# full_charger_v5-3.net
KiCad netlist of a schematic drawn in EAGLE
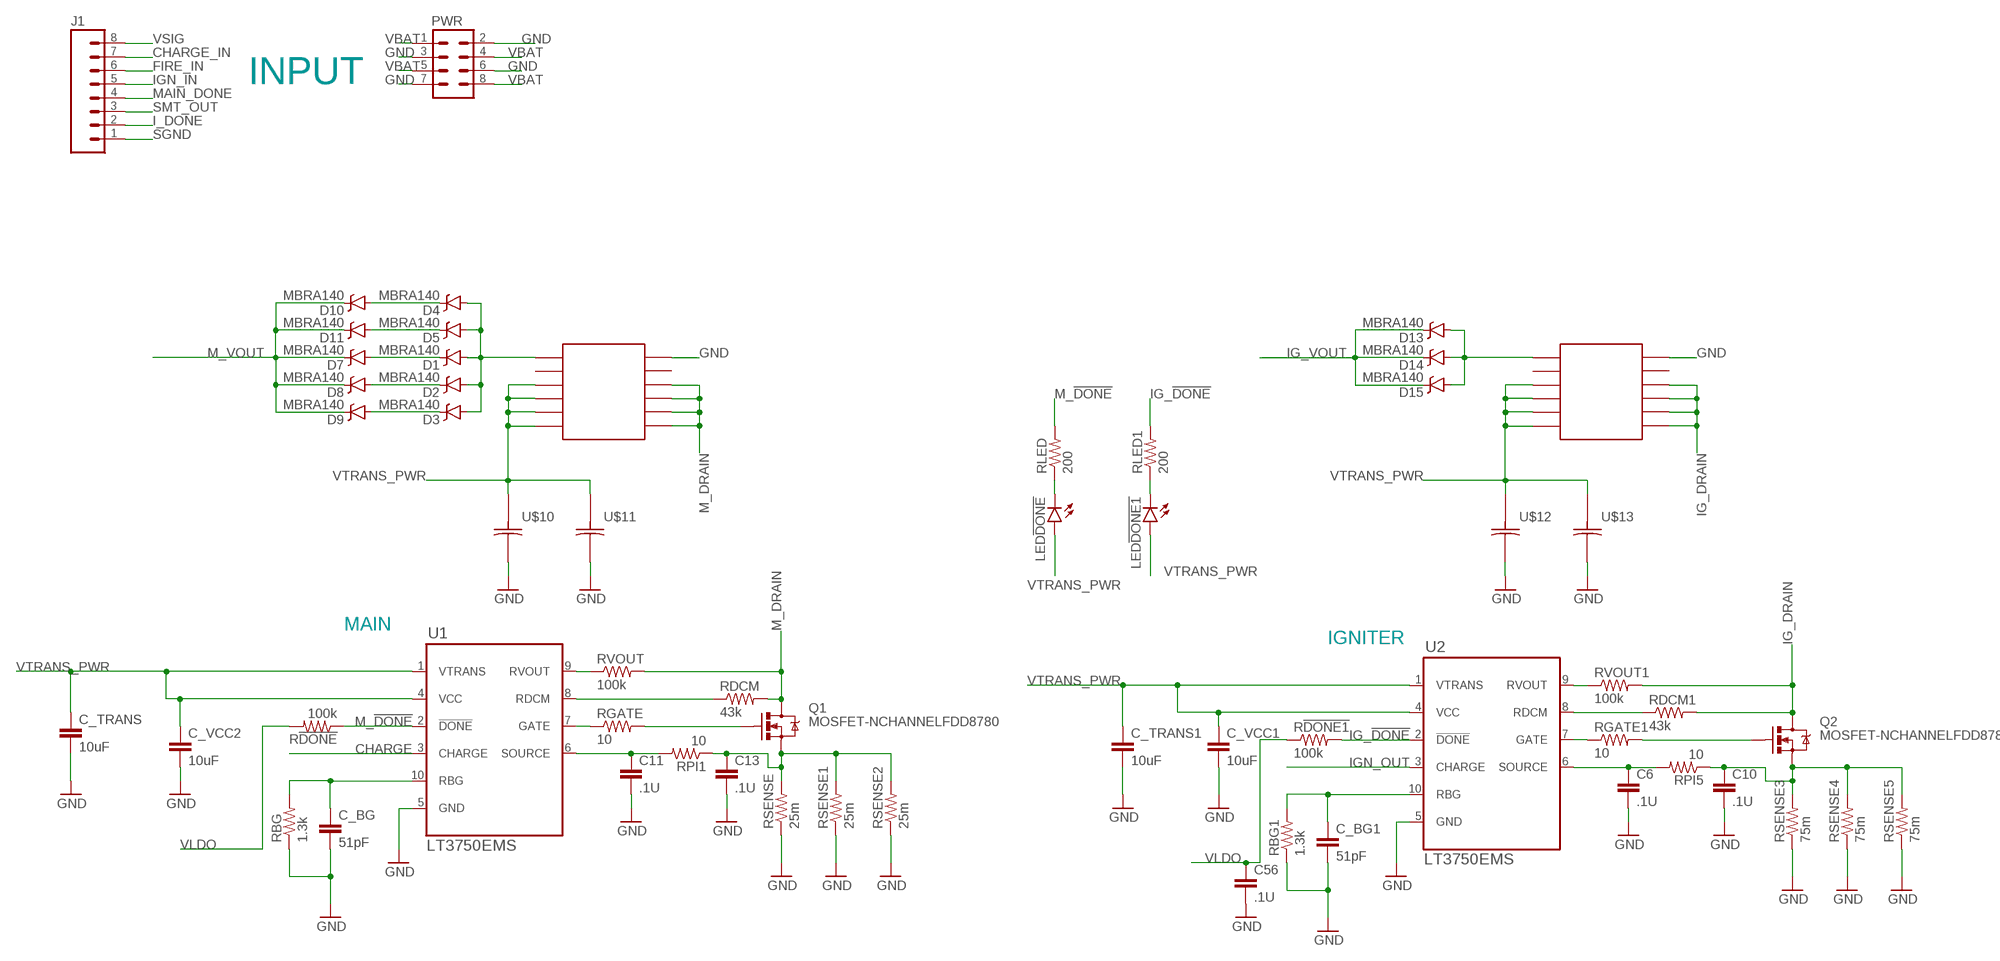
[diagram p0: schematic, sheet 1]
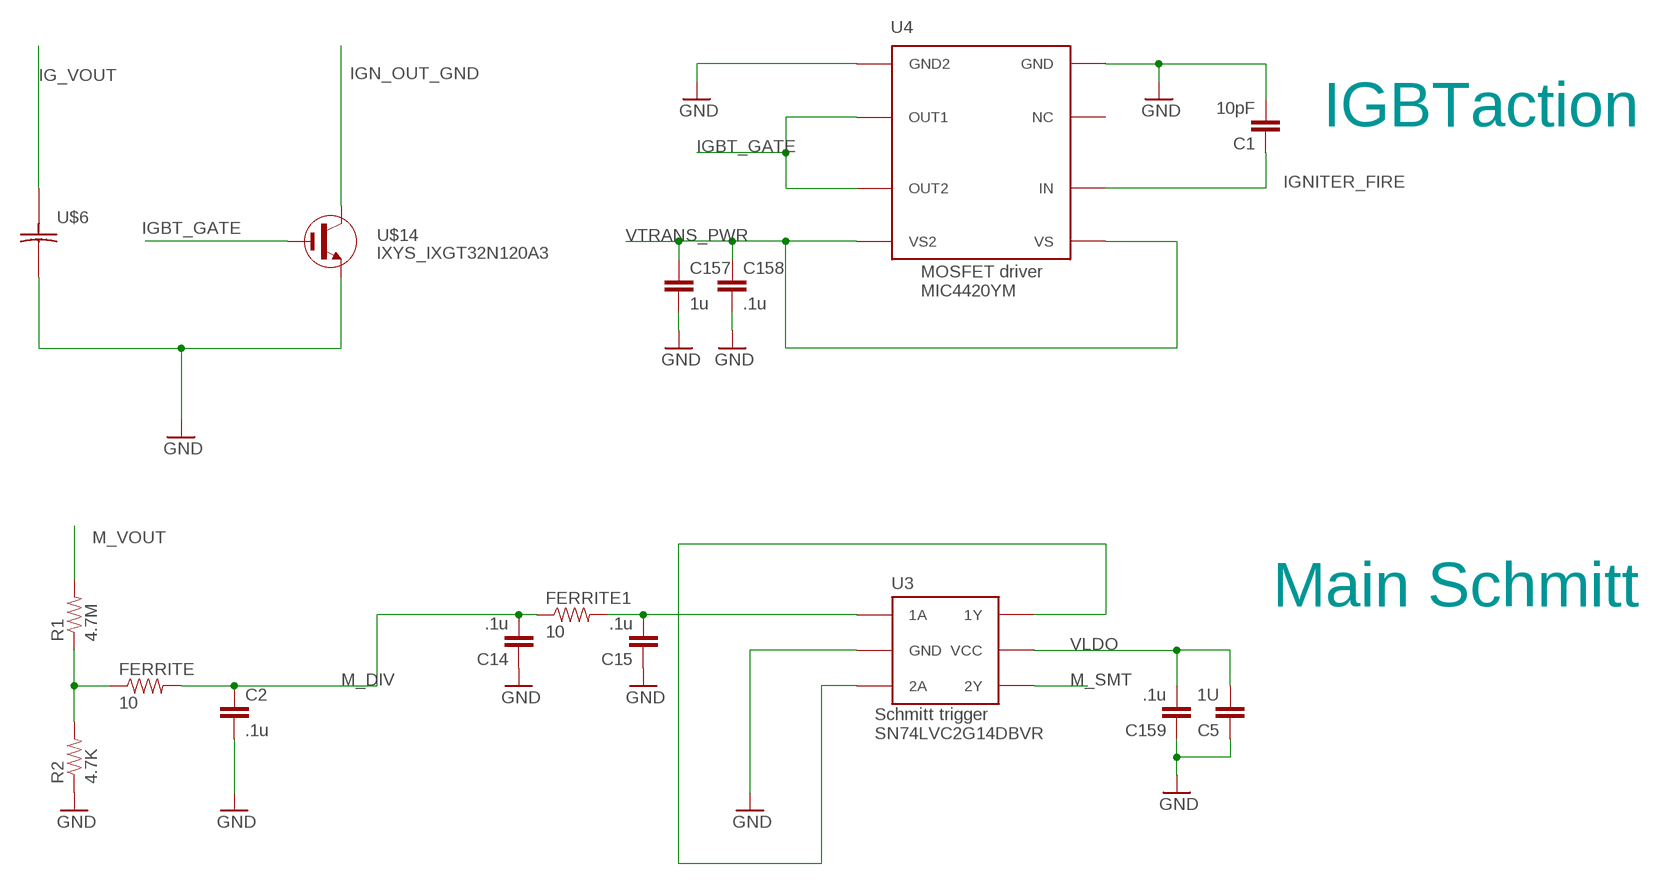
[diagram p1: schematic, sheet 2]
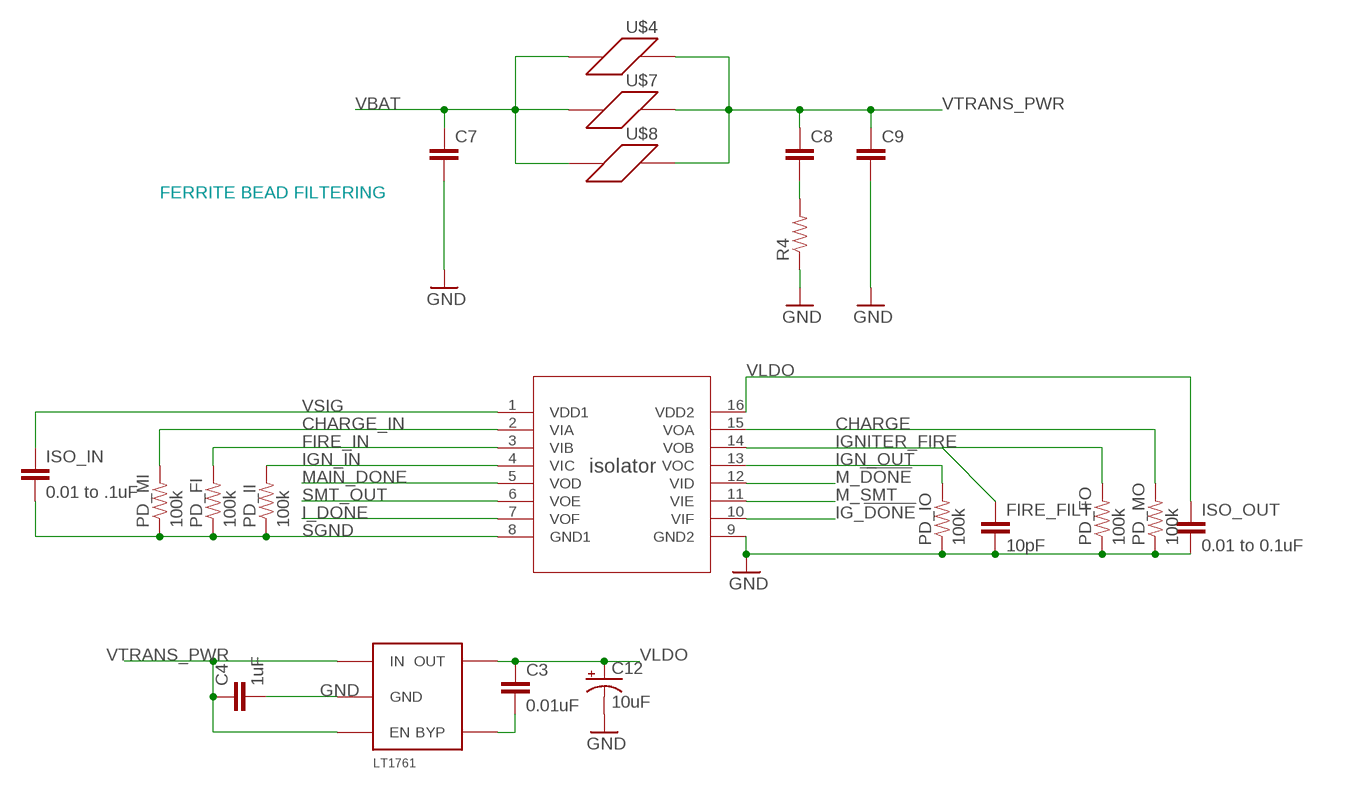
[diagram p2: schematic, sheet 3]

(export (version "E")
  (design (tool "Eeschema 10.0.6"))
  (components
    (comp (ref "ADUM163N")
      (value "ADUM163N1BRZ")
      (footprint "eagle-import:R_16")
      (libsource (lib "eagle-import") (part "ADUM163N1BRZ"))
    )
    (comp (ref "C3")
      (value "0.01uF")
      (footprint "eagle-import:0805")
      (libsource (lib "eagle-import") (part "SparkFun-Passives_CAP0805"))
    )
    (comp (ref "C4")
      (value "1uF")
      (footprint "eagle-import:0805")
      (libsource (lib "eagle-import") (part "SparkFun-Passives_CAP0805"))
    )
    (comp (ref "C7")
      (value "CAP0805")
      (footprint "eagle-import:0805")
      (libsource (lib "eagle-import") (part "CAP0805"))
    )
    (comp (ref "C8")
      (value "CAP0805")
      (footprint "eagle-import:0805")
      (libsource (lib "eagle-import") (part "CAP0805"))
    )
    (comp (ref "C9")
      (value "CAP0805")
      (footprint "eagle-import:0805")
      (libsource (lib "eagle-import") (part "CAP0805"))
    )
    (comp (ref "C12")
      (value "10uF")
      (footprint "eagle-import:EIA3216")
      (libsource (lib "eagle-import") (part "10UF-TANT"))
    )
    (comp (ref "FIRE_FILT")
      (value "10pF")
      (footprint "eagle-import:0805")
      (libsource (lib "eagle-import") (part "SparkFun-Passives_CAP0805"))
    )
    (comp (ref "ISO_IN")
      (value "0.01 to .1uF")
      (footprint "eagle-import:0805")
      (libsource (lib "eagle-import") (part "SparkFun-Passives_CAP0805"))
    )
    (comp (ref "ISO_OUT")
      (value "0.01 to 0.1uF")
      (footprint "eagle-import:0805")
      (libsource (lib "eagle-import") (part "SparkFun-Passives_CAP0805"))
    )
    (comp (ref "LDO")
      (value "LINEAR_LDO_LT1761-X")
      (footprint "eagle-import:SOT-23-5")
      (libsource (lib "eagle-import") (part "LINEAR_LDO_LT1761-X"))
    )
    (comp (ref "PD_FI")
      (value "100k")
      (footprint "eagle-import:0805")
      (libsource (lib "eagle-import") (part "RESISTOR0805-RES"))
    )
    (comp (ref "PD_FO")
      (value "100k")
      (footprint "eagle-import:0805")
      (libsource (lib "eagle-import") (part "RESISTOR0805-RES"))
    )
    (comp (ref "PD_II")
      (value "100k")
      (footprint "eagle-import:0805")
      (libsource (lib "eagle-import") (part "RESISTOR0805-RES"))
    )
    (comp (ref "PD_IO")
      (value "100k")
      (footprint "eagle-import:0805")
      (libsource (lib "eagle-import") (part "RESISTOR0805-RES"))
    )
    (comp (ref "PD_MI")
      (value "100k")
      (footprint "eagle-import:0805")
      (libsource (lib "eagle-import") (part "RESISTOR0805-RES"))
    )
    (comp (ref "PD_MO")
      (value "100k")
      (footprint "eagle-import:0805")
      (libsource (lib "eagle-import") (part "RESISTOR0805-RES"))
    )
    (comp (ref "R4")
      (value "RESISTOR0805-RES")
      (footprint "eagle-import:0805")
      (libsource (lib "eagle-import") (part "RESISTOR0805-RES"))
    )
    (comp (ref "U$4")
      (value "B.L1_FBMJ2125HS420-T")
      (footprint "eagle-import:0805")
      (libsource (lib "eagle-import") (part "B.L1_FBMJ2125HS420-T"))
    )
    (comp (ref "U$7")
      (value "B.L2_FBMH1608HL121-T")
      (footprint "eagle-import:0603")
      (libsource (lib "eagle-import") (part "B.L2_FBMH1608HL121-T"))
    )
    (comp (ref "U$8")
      (value "I.L1_587-3855-1-ND")
      (footprint "eagle-import:1206")
      (libsource (lib "eagle-import") (part "I.L1_587-3855-1-ND"))
    )
    (comp (ref "C1")
      (value "10pF")
      (footprint "eagle-import:0805")
      (libsource (lib "eagle-import") (part "CAP0805"))
    )
    (comp (ref "C2")
      (value ".1u")
      (footprint "eagle-import:0805")
      (libsource (lib "eagle-import") (part "CAP0805"))
    )
    (comp (ref "C5")
      (value "1U")
      (footprint "eagle-import:0805")
      (libsource (lib "eagle-import") (part "CAP0805"))
    )
    (comp (ref "C14")
      (value ".1u")
      (footprint "eagle-import:0805")
      (libsource (lib "eagle-import") (part "CAP0805"))
    )
    (comp (ref "C15")
      (value ".1u")
      (footprint "eagle-import:0805")
      (libsource (lib "eagle-import") (part "CAP0805"))
    )
    (comp (ref "C157")
      (value "1u")
      (footprint "eagle-import:0805")
      (libsource (lib "eagle-import") (part "CAP0805"))
    )
    (comp (ref "C158")
      (value ".1u")
      (footprint "eagle-import:0805")
      (libsource (lib "eagle-import") (part "CAP0805"))
    )
    (comp (ref "C159")
      (value ".1u")
      (footprint "eagle-import:0805")
      (libsource (lib "eagle-import") (part "CAP0805"))
    )
    (comp (ref "FERRITE")
      (value "10")
      (footprint "eagle-import:0805")
      (libsource (lib "eagle-import") (part "RESISTOR0805-RES"))
    )
    (comp (ref "FERRITE1")
      (value "10")
      (footprint "eagle-import:0805")
      (libsource (lib "eagle-import") (part "RESISTOR0805-RES"))
    )
    (comp (ref "R1")
      (value "4.7M")
      (footprint "eagle-import:R2010")
      (libsource (lib "eagle-import") (part "SparkFun-Passives_RESISTOR2010"))
    )
    (comp (ref "R2")
      (value "4.7K")
      (footprint "eagle-import:R2010")
      (libsource (lib "eagle-import") (part "SparkFun-Passives_RESISTOR2010"))
    )
    (comp (ref "U$6")
      (value "KEMET_LDEQH3100KA5N00")
      (footprint "eagle-import:KEMET_F3078")
      (libsource (lib "eagle-import") (part "KEMET_LDEQH3100KA5N00"))
    )
    (comp (ref "U$14")
      (value "IXYS_IXGT32N120A3")
      (footprint "eagle-import:TO-268")
      (libsource (lib "eagle-import") (part "IXYS_IXGT32N120A3"))
    )
    (comp (ref "U3")
      (value "TI_SCHMITTRIGGER_SN74")
      (footprint "eagle-import:SOT-23-6")
      (libsource (lib "eagle-import") (part "TI_SCHMITTRIGGER_SN74"))
    )
    (comp (ref "U4")
      (value "MICREL_MOSFETDRIVER_MIC4420")
      (footprint "eagle-import:8-SOIC")
      (libsource (lib "eagle-import") (part "MICREL_MOSFETDRIVER_MIC4420"))
    )
    (comp (ref "C6")
      (value ".1U")
      (footprint "eagle-import:0805")
      (libsource (lib "eagle-import") (part "CAP0805"))
    )
    (comp (ref "C10")
      (value ".1U")
      (footprint "eagle-import:0805")
      (libsource (lib "eagle-import") (part "CAP0805"))
    )
    (comp (ref "C11")
      (value ".1U")
      (footprint "eagle-import:0805")
      (libsource (lib "eagle-import") (part "CAP0805"))
    )
    (comp (ref "C13")
      (value ".1U")
      (footprint "eagle-import:0805")
      (libsource (lib "eagle-import") (part "CAP0805"))
    )
    (comp (ref "C56")
      (value ".1U")
      (footprint "eagle-import:0805")
      (libsource (lib "eagle-import") (part "CAP0805"))
    )
    (comp (ref "C_BG")
      (value "51pF")
      (footprint "eagle-import:0805")
      (libsource (lib "eagle-import") (part "CAP0805"))
    )
    (comp (ref "C_BG1")
      (value "51pF")
      (footprint "eagle-import:0805")
      (libsource (lib "eagle-import") (part "CAP0805"))
    )
    (comp (ref "C_TRANS")
      (value "10uF")
      (footprint "eagle-import:0805")
      (libsource (lib "eagle-import") (part "CAP0805"))
    )
    (comp (ref "C_TRANS1")
      (value "10uF")
      (footprint "eagle-import:0805")
      (libsource (lib "eagle-import") (part "CAP0805"))
    )
    (comp (ref "C_VCC1")
      (value "10uF")
      (footprint "eagle-import:0805")
      (libsource (lib "eagle-import") (part "CAP0805"))
    )
    (comp (ref "C_VCC2")
      (value "10uF")
      (footprint "eagle-import:0805")
      (libsource (lib "eagle-import") (part "CAP0805"))
    )
    (comp (ref "D1")
      (value "MBRA140")
      (footprint "eagle-import:SMA-DIODE")
      (libsource (lib "eagle-import") (part "MBRA140"))
    )
    (comp (ref "D2")
      (value "MBRA140")
      (footprint "eagle-import:SMA-DIODE")
      (libsource (lib "eagle-import") (part "MBRA140"))
    )
    (comp (ref "D3")
      (value "MBRA140")
      (footprint "eagle-import:SMA-DIODE")
      (libsource (lib "eagle-import") (part "MBRA140"))
    )
    (comp (ref "D4")
      (value "MBRA140")
      (footprint "eagle-import:SMA-DIODE")
      (libsource (lib "eagle-import") (part "MBRA140"))
    )
    (comp (ref "D5")
      (value "MBRA140")
      (footprint "eagle-import:SMA-DIODE")
      (libsource (lib "eagle-import") (part "MBRA140"))
    )
    (comp (ref "D7")
      (value "MBRA140")
      (footprint "eagle-import:SMA-DIODE")
      (libsource (lib "eagle-import") (part "MBRA140"))
    )
    (comp (ref "D8")
      (value "MBRA140")
      (footprint "eagle-import:SMA-DIODE")
      (libsource (lib "eagle-import") (part "MBRA140"))
    )
    (comp (ref "D9")
      (value "MBRA140")
      (footprint "eagle-import:SMA-DIODE")
      (libsource (lib "eagle-import") (part "MBRA140"))
    )
    (comp (ref "D10")
      (value "MBRA140")
      (footprint "eagle-import:SMA-DIODE")
      (libsource (lib "eagle-import") (part "MBRA140"))
    )
    (comp (ref "D11")
      (value "MBRA140")
      (footprint "eagle-import:SMA-DIODE")
      (libsource (lib "eagle-import") (part "MBRA140"))
    )
    (comp (ref "D13")
      (value "MBRA140")
      (footprint "eagle-import:SMA-DIODE")
      (libsource (lib "eagle-import") (part "MBRA140"))
    )
    (comp (ref "D14")
      (value "MBRA140")
      (footprint "eagle-import:SMA-DIODE")
      (libsource (lib "eagle-import") (part "MBRA140"))
    )
    (comp (ref "D15")
      (value "MBRA140")
      (footprint "eagle-import:SMA-DIODE")
      (libsource (lib "eagle-import") (part "MBRA140"))
    )
    (comp (ref "J1")
      (value "M08")
      (footprint "eagle-import:1X08_ROUND")
      (libsource (lib "eagle-import") (part "M08"))
    )
    (comp (ref "LED!DONE")
      (value "LED1206")
      (footprint "eagle-import:LED-1206")
      (libsource (lib "eagle-import") (part "LED1206"))
    )
    (comp (ref "LED!DONE1")
      (value "LED1206")
      (footprint "eagle-import:LED-1206")
      (libsource (lib "eagle-import") (part "LED1206"))
    )
    (comp (ref "PWR")
      (value "M04X2")
      (footprint "eagle-import:2X4")
      (libsource (lib "eagle-import") (part "M04X2"))
    )
    (comp (ref "Q1")
      (value "MOSFET-NCHANNELFDD8780")
      (footprint "eagle-import:DPAK")
      (libsource (lib "eagle-import") (part "MOSFET-NCHANNELFDD8780"))
    )
    (comp (ref "Q2")
      (value "MOSFET-NCHANNELFDD8780")
      (footprint "eagle-import:DPAK")
      (libsource (lib "eagle-import") (part "MOSFET-NCHANNELFDD8780"))
    )
    (comp (ref "R!DONE")
      (value "100k")
      (footprint "eagle-import:0805")
      (libsource (lib "eagle-import") (part "SparkFun-Resistors_RESISTOR0805-RES"))
    )
    (comp (ref "R!DONE1")
      (value "100k")
      (footprint "eagle-import:0805")
      (libsource (lib "eagle-import") (part "SparkFun-Resistors_RESISTOR0805-RES"))
    )
    (comp (ref "RBG")
      (value "1.3k")
      (footprint "eagle-import:0805")
      (libsource (lib "eagle-import") (part "SparkFun-Resistors_RESISTOR0805-RES"))
    )
    (comp (ref "RBG1")
      (value "1.3k")
      (footprint "eagle-import:0805")
      (libsource (lib "eagle-import") (part "SparkFun-Resistors_RESISTOR0805-RES"))
    )
    (comp (ref "RDCM")
      (value "43k")
      (footprint "eagle-import:0805")
      (libsource (lib "eagle-import") (part "SparkFun-Resistors_RESISTOR0805-RES"))
    )
    (comp (ref "RDCM1")
      (value "43k")
      (footprint "eagle-import:0805")
      (libsource (lib "eagle-import") (part "SparkFun-Resistors_RESISTOR0805-RES"))
    )
    (comp (ref "RGATE")
      (value "10")
      (footprint "eagle-import:0805")
      (libsource (lib "eagle-import") (part "SparkFun-Resistors_RESISTOR0805-RES"))
    )
    (comp (ref "RGATE1")
      (value "10")
      (footprint "eagle-import:0805")
      (libsource (lib "eagle-import") (part "SparkFun-Resistors_RESISTOR0805-RES"))
    )
    (comp (ref "RLED")
      (value "200")
      (footprint "eagle-import:0805")
      (libsource (lib "eagle-import") (part "RESISTOR0805-RES"))
    )
    (comp (ref "RLED1")
      (value "200")
      (footprint "eagle-import:0805")
      (libsource (lib "eagle-import") (part "RESISTOR0805-RES"))
    )
    (comp (ref "RPI1")
      (value "10")
      (footprint "eagle-import:0805")
      (libsource (lib "eagle-import") (part "SparkFun-Resistors_RESISTOR0805-RES"))
    )
    (comp (ref "RPI5")
      (value "10")
      (footprint "eagle-import:0805")
      (libsource (lib "eagle-import") (part "SparkFun-Resistors_RESISTOR0805-RES"))
    )
    (comp (ref "RSENSE")
      (value "25m")
      (footprint "eagle-import:1206")
      (libsource (lib "eagle-import") (part "RESISTOR1206"))
    )
    (comp (ref "RSENSE1")
      (value "25m")
      (footprint "eagle-import:1206")
      (libsource (lib "eagle-import") (part "RESISTOR1206"))
    )
    (comp (ref "RSENSE2")
      (value "25m")
      (footprint "eagle-import:1206")
      (libsource (lib "eagle-import") (part "RESISTOR1206"))
    )
    (comp (ref "RSENSE3")
      (value "75m")
      (footprint "eagle-import:1206")
      (libsource (lib "eagle-import") (part "RESISTOR1206"))
    )
    (comp (ref "RSENSE4")
      (value "75m")
      (footprint "eagle-import:1206")
      (libsource (lib "eagle-import") (part "RESISTOR1206"))
    )
    (comp (ref "RSENSE5")
      (value "75m")
      (footprint "eagle-import:1206")
      (libsource (lib "eagle-import") (part "RESISTOR1206"))
    )
    (comp (ref "RVOUT")
      (value "100k")
      (footprint "eagle-import:0805")
      (libsource (lib "eagle-import") (part "SparkFun-Resistors_RESISTOR0805-RES"))
    )
    (comp (ref "RVOUT1")
      (value "100k")
      (footprint "eagle-import:0805")
      (libsource (lib "eagle-import") (part "SparkFun-Resistors_RESISTOR0805-RES"))
    )
    (comp (ref "U$1")
      (value "COILCRAFT_DA2034")
      (footprint "eagle-import:DA2034")
      (libsource (lib "eagle-import") (part "COILCRAFT_DA2034"))
    )
    (comp (ref "U$2")
      (value "COILCRAFT_DA2033")
      (footprint "eagle-import:DA2033")
      (libsource (lib "eagle-import") (part "COILCRAFT_DA2033"))
    )
    (comp (ref "U$10")
      (value "PANASONIC_16SVPG270M")
      (footprint "eagle-import:PANASONIC_SVPG")
      (libsource (lib "eagle-import") (part "PANASONIC_16SVPG270M"))
    )
    (comp (ref "U$11")
      (value "PANASONIC_16SVPG270M")
      (footprint "eagle-import:PANASONIC_SVPG")
      (libsource (lib "eagle-import") (part "PANASONIC_16SVPG270M"))
    )
    (comp (ref "U$12")
      (value "PANASONIC_16SVPG270M")
      (footprint "eagle-import:PANASONIC_SVPG")
      (libsource (lib "eagle-import") (part "PANASONIC_16SVPG270M"))
    )
    (comp (ref "U$13")
      (value "PANASONIC_16SVPG270M")
      (footprint "eagle-import:PANASONIC_SVPG")
      (libsource (lib "eagle-import") (part "PANASONIC_16SVPG270M"))
    )
    (comp (ref "U1")
      (value "LT3750EMS")
      (footprint "eagle-import:MSOP10")
      (libsource (lib "eagle-import") (part "LT3750EMS"))
    )
    (comp (ref "U2")
      (value "LT3750EMS")
      (footprint "eagle-import:MSOP10")
      (libsource (lib "eagle-import") (part "LT3750EMS"))
    )
  )
  (nets
    (net (code "1") (name "CHARGE") (class "Default")
      (node (ref "ADUM163N") (pin "15") (pinfunction "VOA_15") (pintype "passive"))
      (node (ref "PD_MO") (pin "2") (pinfunction "2_2") (pintype "passive"))
      (node (ref "U1") (pin "3") (pinfunction "CHARGE_3") (pintype "bidirectional"))
    )
    (net (code "2") (name "CHARGE_IN") (class "Default")
      (node (ref "ADUM163N") (pin "2") (pinfunction "VIA_2") (pintype "passive"))
      (node (ref "J1") (pin "7") (pinfunction "7_7") (pintype "passive"))
      (node (ref "PD_MI") (pin "2") (pinfunction "2_2") (pintype "passive"))
    )
    (net (code "3") (name "FIRE_IN") (class "Default")
      (node (ref "ADUM163N") (pin "3") (pinfunction "VIB_3") (pintype "passive"))
      (node (ref "J1") (pin "6") (pinfunction "6_6") (pintype "passive"))
      (node (ref "PD_FI") (pin "2") (pinfunction "2_2") (pintype "passive"))
    )
    (net (code "4") (name "GND") (class "Default")
      (node (ref "ADUM163N") (pin "9") (pinfunction "GND2_9") (pintype "passive"))
      (node (ref "C1") (pin "2") (pinfunction "2_2") (pintype "passive"))
      (node (ref "C10") (pin "2") (pinfunction "2_2") (pintype "passive"))
      (node (ref "C11") (pin "2") (pinfunction "2_2") (pintype "passive"))
      (node (ref "C12") (pin "C") (pinfunction "-_C") (pintype "passive"))
      (node (ref "C13") (pin "2") (pinfunction "2_2") (pintype "passive"))
      (node (ref "C14") (pin "1") (pinfunction "1_1") (pintype "passive"))
      (node (ref "C15") (pin "1") (pinfunction "1_1") (pintype "passive"))
      (node (ref "C157") (pin "2") (pinfunction "2_2") (pintype "passive"))
      (node (ref "C158") (pin "2") (pinfunction "2_2") (pintype "passive"))
      (node (ref "C159") (pin "1") (pinfunction "1_1") (pintype "passive"))
      (node (ref "C2") (pin "2") (pinfunction "2_2") (pintype "passive"))
      (node (ref "C4") (pin "2") (pinfunction "2_2") (pintype "passive"))
      (node (ref "C5") (pin "1") (pinfunction "1_1") (pintype "passive"))
      (node (ref "C56") (pin "2") (pinfunction "2_2") (pintype "passive"))
      (node (ref "C6") (pin "2") (pinfunction "2_2") (pintype "passive"))
      (node (ref "C7") (pin "2") (pinfunction "2_2") (pintype "passive"))
      (node (ref "C9") (pin "2") (pinfunction "2_2") (pintype "passive"))
      (node (ref "C_BG") (pin "2") (pinfunction "2_2") (pintype "passive"))
      (node (ref "C_BG1") (pin "2") (pinfunction "2_2") (pintype "passive"))
      (node (ref "C_TRANS") (pin "2") (pinfunction "2_2") (pintype "passive"))
      (node (ref "C_TRANS1") (pin "2") (pinfunction "2_2") (pintype "passive"))
      (node (ref "C_VCC1") (pin "2") (pinfunction "2_2") (pintype "passive"))
      (node (ref "C_VCC2") (pin "2") (pinfunction "2_2") (pintype "passive"))
      (node (ref "FIRE_FILT") (pin "2") (pinfunction "2_2") (pintype "passive"))
      (node (ref "ISO_OUT") (pin "2") (pinfunction "2_2") (pintype "passive"))
      (node (ref "LDO") (pin "P$2") (pinfunction "GND_P$2") (pintype "bidirectional"))
      (node (ref "PD_FO") (pin "1") (pinfunction "1_1") (pintype "passive"))
      (node (ref "PD_IO") (pin "1") (pinfunction "1_1") (pintype "passive"))
      (node (ref "PD_MO") (pin "1") (pinfunction "1_1") (pintype "passive"))
      (node (ref "PWR") (pin "2") (pinfunction "2_2") (pintype "passive"))
      (node (ref "PWR") (pin "3") (pinfunction "3_3") (pintype "passive"))
      (node (ref "PWR") (pin "6") (pinfunction "6_6") (pintype "passive"))
      (node (ref "PWR") (pin "7") (pinfunction "7_7") (pintype "passive"))
      (node (ref "R2") (pin "1") (pinfunction "1_1") (pintype "passive"))
      (node (ref "R4") (pin "1") (pinfunction "1_1") (pintype "passive"))
      (node (ref "RBG") (pin "1") (pinfunction "1_1") (pintype "passive"))
      (node (ref "RBG1") (pin "1") (pinfunction "1_1") (pintype "passive"))
      (node (ref "RSENSE") (pin "1") (pinfunction "1_1") (pintype "passive"))
      (node (ref "RSENSE1") (pin "1") (pinfunction "1_1") (pintype "passive"))
      (node (ref "RSENSE2") (pin "1") (pinfunction "1_1") (pintype "passive"))
      (node (ref "RSENSE3") (pin "1") (pinfunction "1_1") (pintype "passive"))
      (node (ref "RSENSE4") (pin "1") (pinfunction "1_1") (pintype "passive"))
      (node (ref "RSENSE5") (pin "1") (pinfunction "1_1") (pintype "passive"))
      (node (ref "U$1") (pin "P$12") (pinfunction "P$12_P$12") (pintype "bidirectional"))
      (node (ref "U$10") (pin "NEG") (pinfunction "NEG_NEG") (pintype "bidirectional"))
      (node (ref "U$11") (pin "NEG") (pinfunction "NEG_NEG") (pintype "bidirectional"))
      (node (ref "U$12") (pin "NEG") (pinfunction "NEG_NEG") (pintype "bidirectional"))
      (node (ref "U$13") (pin "NEG") (pinfunction "NEG_NEG") (pintype "bidirectional"))
      (node (ref "U$14") (pin "3") (pinfunction "E_3") (pintype "passive"))
      (node (ref "U$2") (pin "P$12") (pinfunction "P$12_P$12") (pintype "bidirectional"))
      (node (ref "U$6") (pin "NEG") (pinfunction "NEG_NEG") (pintype "bidirectional"))
      (node (ref "U1") (pin "5") (pinfunction "GND_5") (pintype "passive"))
      (node (ref "U2") (pin "5") (pinfunction "GND_5") (pintype "passive"))
      (node (ref "U3") (pin "P$2") (pinfunction "GND_P$2") (pintype "bidirectional"))
      (node (ref "U4") (pin "P$4") (pinfunction "GND_P$4") (pintype "bidirectional"))
      (node (ref "U4") (pin "P$5") (pinfunction "GND2_P$5") (pintype "bidirectional"))
    )
    (net (code "5") (name "IGBT_GATE") (class "Default")
      (node (ref "U$14") (pin "1") (pinfunction "G_1") (pintype "passive"))
      (node (ref "U4") (pin "P$6") (pinfunction "OUT1_P$6") (pintype "bidirectional"))
      (node (ref "U4") (pin "P$7") (pinfunction "OUT2_P$7") (pintype "bidirectional"))
    )
    (net (code "6") (name "IGNITER_FIRE") (class "Default")
      (node (ref "ADUM163N") (pin "14") (pinfunction "VOB_14") (pintype "passive"))
      (node (ref "C1") (pin "1") (pinfunction "1_1") (pintype "passive"))
      (node (ref "FIRE_FILT") (pin "1") (pinfunction "1_1") (pintype "passive"))
      (node (ref "PD_FO") (pin "2") (pinfunction "2_2") (pintype "passive"))
      (node (ref "U4") (pin "P$2") (pinfunction "IN_P$2") (pintype "bidirectional"))
    )
    (net (code "7") (name "IGN_IN") (class "Default")
      (node (ref "ADUM163N") (pin "4") (pinfunction "VIC_4") (pintype "passive"))
      (node (ref "J1") (pin "5") (pinfunction "5_5") (pintype "passive"))
      (node (ref "PD_II") (pin "2") (pinfunction "2_2") (pintype "passive"))
    )
    (net (code "8") (name "IGN_OUT") (class "Default")
      (node (ref "ADUM163N") (pin "13") (pinfunction "VOC_13") (pintype "passive"))
      (node (ref "PD_IO") (pin "2") (pinfunction "2_2") (pintype "passive"))
      (node (ref "U2") (pin "3") (pinfunction "CHARGE_3") (pintype "bidirectional"))
    )
    (net (code "9") (name "IGN_OUT_GND") (class "Default")
      (node (ref "U$14") (pin "2") (pinfunction "C_2") (pintype "passive"))
    )
    (net (code "10") (name "IG_DRAIN") (class "Default")
      (node (ref "Q2") (pin "4") (pinfunction "D_4") (pintype "passive"))
      (node (ref "RDCM1") (pin "2") (pinfunction "2_2") (pintype "passive"))
      (node (ref "RVOUT1") (pin "2") (pinfunction "2_2") (pintype "passive"))
      (node (ref "U$2") (pin "P$10") (pinfunction "P$10_P$10") (pintype "bidirectional"))
      (node (ref "U$2") (pin "P$7") (pinfunction "P$7_P$7") (pintype "bidirectional"))
      (node (ref "U$2") (pin "P$8") (pinfunction "P$8_P$8") (pintype "bidirectional"))
      (node (ref "U$2") (pin "P$9") (pinfunction "P$9_P$9") (pintype "bidirectional"))
    )
    (net (code "11") (name "IG_VOUT") (class "Default")
      (node (ref "D13") (pin "C") (pinfunction "C_C") (pintype "passive"))
      (node (ref "D14") (pin "C") (pinfunction "C_C") (pintype "passive"))
      (node (ref "D15") (pin "C") (pinfunction "C_C") (pintype "passive"))
      (node (ref "U$6") (pin "POS") (pinfunction "POS_POS") (pintype "bidirectional"))
    )
    (net (code "12") (name "IG_~{DONE}") (class "Default")
      (node (ref "ADUM163N") (pin "10") (pinfunction "VIF_10") (pintype "passive"))
      (node (ref "R!DONE1") (pin "2") (pinfunction "2_2") (pintype "passive"))
      (node (ref "RLED1") (pin "2") (pinfunction "2_2") (pintype "passive"))
      (node (ref "U2") (pin "2") (pinfunction "~{DONE}_2") (pintype "bidirectional"))
    )
    (net (code "13") (name "I_DONE") (class "Default")
      (node (ref "ADUM163N") (pin "7") (pinfunction "VOF_7") (pintype "passive"))
      (node (ref "J1") (pin "2") (pinfunction "2_2") (pintype "passive"))
    )
    (net (code "14") (name "MAIN_DONE") (class "Default")
      (node (ref "ADUM163N") (pin "5") (pinfunction "VOD_5") (pintype "passive"))
      (node (ref "J1") (pin "4") (pinfunction "4_4") (pintype "passive"))
    )
    (net (code "15") (name "M_DIV") (class "Default")
      (node (ref "C14") (pin "2") (pinfunction "2_2") (pintype "passive"))
      (node (ref "C2") (pin "1") (pinfunction "1_1") (pintype "passive"))
      (node (ref "FERRITE") (pin "2") (pinfunction "2_2") (pintype "passive"))
      (node (ref "FERRITE1") (pin "1") (pinfunction "1_1") (pintype "passive"))
    )
    (net (code "16") (name "M_DRAIN") (class "Default")
      (node (ref "Q1") (pin "4") (pinfunction "D_4") (pintype "passive"))
      (node (ref "RDCM") (pin "2") (pinfunction "2_2") (pintype "passive"))
      (node (ref "RVOUT") (pin "2") (pinfunction "2_2") (pintype "passive"))
      (node (ref "U$1") (pin "P$10") (pinfunction "P$10_P$10") (pintype "bidirectional"))
      (node (ref "U$1") (pin "P$7") (pinfunction "P$7_P$7") (pintype "bidirectional"))
      (node (ref "U$1") (pin "P$8") (pinfunction "P$8_P$8") (pintype "bidirectional"))
      (node (ref "U$1") (pin "P$9") (pinfunction "P$9_P$9") (pintype "bidirectional"))
    )
    (net (code "17") (name "M_SMT") (class "Default")
      (node (ref "ADUM163N") (pin "11") (pinfunction "VIE_11") (pintype "passive"))
      (node (ref "U3") (pin "P$4") (pinfunction "2Y_P$4") (pintype "bidirectional"))
    )
    (net (code "18") (name "M_VOUT") (class "Default")
      (node (ref "D10") (pin "C") (pinfunction "C_C") (pintype "passive"))
      (node (ref "D11") (pin "C") (pinfunction "C_C") (pintype "passive"))
      (node (ref "D7") (pin "C") (pinfunction "C_C") (pintype "passive"))
      (node (ref "D8") (pin "C") (pinfunction "C_C") (pintype "passive"))
      (node (ref "D9") (pin "C") (pinfunction "C_C") (pintype "passive"))
      (node (ref "R1") (pin "2") (pinfunction "2_2") (pintype "passive"))
    )
    (net (code "19") (name "M_~{DONE}") (class "Default")
      (node (ref "ADUM163N") (pin "12") (pinfunction "VID_12") (pintype "passive"))
      (node (ref "R!DONE") (pin "1") (pinfunction "1_1") (pintype "passive"))
      (node (ref "RLED") (pin "2") (pinfunction "2_2") (pintype "passive"))
      (node (ref "U1") (pin "2") (pinfunction "~{DONE}_2") (pintype "bidirectional"))
    )
    (net (code "20") (name "Net-(C8-Pad2)") (class "Default")
      (node (ref "C8") (pin "2") (pinfunction "2_2") (pintype "passive"))
      (node (ref "R4") (pin "2") (pinfunction "2_2") (pintype "passive"))
    )
    (net (code "21") (name "Net-(D1-PadA)") (class "Default")
      (node (ref "D1") (pin "A") (pinfunction "A_A") (pintype "passive"))
      (node (ref "D2") (pin "A") (pinfunction "A_A") (pintype "passive"))
      (node (ref "D3") (pin "A") (pinfunction "A_A") (pintype "passive"))
      (node (ref "D4") (pin "A") (pinfunction "A_A") (pintype "passive"))
      (node (ref "D5") (pin "A") (pinfunction "A_A") (pintype "passive"))
      (node (ref "U$1") (pin "P$1") (pinfunction "P$1_P$1") (pintype "bidirectional"))
    )
    (net (code "22") (name "Net-(D1-PadC)") (class "Default")
      (node (ref "D1") (pin "C") (pinfunction "C_C") (pintype "passive"))
      (node (ref "D7") (pin "A") (pinfunction "A_A") (pintype "passive"))
    )
    (net (code "23") (name "Net-(D2-PadC)") (class "Default")
      (node (ref "D2") (pin "C") (pinfunction "C_C") (pintype "passive"))
      (node (ref "D8") (pin "A") (pinfunction "A_A") (pintype "passive"))
    )
    (net (code "24") (name "Net-(D3-PadC)") (class "Default")
      (node (ref "D3") (pin "C") (pinfunction "C_C") (pintype "passive"))
      (node (ref "D9") (pin "A") (pinfunction "A_A") (pintype "passive"))
    )
    (net (code "25") (name "Net-(D10-PadA)") (class "Default")
      (node (ref "D10") (pin "A") (pinfunction "A_A") (pintype "passive"))
      (node (ref "D4") (pin "C") (pinfunction "C_C") (pintype "passive"))
    )
    (net (code "26") (name "Net-(D11-PadA)") (class "Default")
      (node (ref "D11") (pin "A") (pinfunction "A_A") (pintype "passive"))
      (node (ref "D5") (pin "C") (pinfunction "C_C") (pintype "passive"))
    )
    (net (code "27") (name "Net-(D13-PadA)") (class "Default")
      (node (ref "D13") (pin "A") (pinfunction "A_A") (pintype "passive"))
      (node (ref "D14") (pin "A") (pinfunction "A_A") (pintype "passive"))
      (node (ref "D15") (pin "A") (pinfunction "A_A") (pintype "passive"))
      (node (ref "U$2") (pin "P$1") (pinfunction "P$1_P$1") (pintype "bidirectional"))
    )
    (net (code "28") (name "Net-(FERRITE-Pad1)") (class "Default")
      (node (ref "FERRITE") (pin "1") (pinfunction "1_1") (pintype "passive"))
      (node (ref "R1") (pin "1") (pinfunction "1_1") (pintype "passive"))
      (node (ref "R2") (pin "2") (pinfunction "2_2") (pintype "passive"))
    )
    (net (code "29") (name "Net-(LDO-BYP)") (class "Default")
      (node (ref "C3") (pin "2") (pinfunction "2_2") (pintype "passive"))
      (node (ref "LDO") (pin "P$4") (pinfunction "BYP_P$4") (pintype "bidirectional"))
    )
    (net (code "30") (name "Net-(LED!DONE-PadC)") (class "Default")
      (node (ref "LED!DONE") (pin "C") (pinfunction "C_C") (pintype "passive"))
      (node (ref "RLED") (pin "1") (pinfunction "1_1") (pintype "passive"))
    )
    (net (code "31") (name "Net-(LED!DONE1-PadC)") (class "Default")
      (node (ref "LED!DONE1") (pin "C") (pinfunction "C_C") (pintype "passive"))
      (node (ref "RLED1") (pin "1") (pinfunction "1_1") (pintype "passive"))
    )
    (net (code "32") (name "Net-(Q1-G)") (class "Default")
      (node (ref "Q1") (pin "1") (pinfunction "G_1") (pintype "passive"))
      (node (ref "RGATE") (pin "2") (pinfunction "2_2") (pintype "passive"))
    )
    (net (code "33") (name "Net-(Q1-S)") (class "Default")
      (node (ref "C13") (pin "1") (pinfunction "1_1") (pintype "passive"))
      (node (ref "Q1") (pin "3") (pinfunction "S_3") (pintype "passive"))
      (node (ref "RPI1") (pin "1") (pinfunction "1_1") (pintype "passive"))
      (node (ref "RSENSE") (pin "2") (pinfunction "2_2") (pintype "passive"))
      (node (ref "RSENSE1") (pin "2") (pinfunction "2_2") (pintype "passive"))
      (node (ref "RSENSE2") (pin "2") (pinfunction "2_2") (pintype "passive"))
    )
    (net (code "34") (name "Net-(Q2-G)") (class "Default")
      (node (ref "Q2") (pin "1") (pinfunction "G_1") (pintype "passive"))
      (node (ref "RGATE1") (pin "2") (pinfunction "2_2") (pintype "passive"))
    )
    (net (code "35") (name "Net-(Q2-S)") (class "Default")
      (node (ref "C10") (pin "1") (pinfunction "1_1") (pintype "passive"))
      (node (ref "Q2") (pin "3") (pinfunction "S_3") (pintype "passive"))
      (node (ref "RPI5") (pin "1") (pinfunction "1_1") (pintype "passive"))
      (node (ref "RSENSE3") (pin "2") (pinfunction "2_2") (pintype "passive"))
      (node (ref "RSENSE4") (pin "2") (pinfunction "2_2") (pintype "passive"))
      (node (ref "RSENSE5") (pin "2") (pinfunction "2_2") (pintype "passive"))
    )
    (net (code "36") (name "Net-(U1-GATE)") (class "Default")
      (node (ref "RGATE") (pin "1") (pinfunction "1_1") (pintype "passive"))
      (node (ref "U1") (pin "7") (pinfunction "GATE_7") (pintype "bidirectional"))
    )
    (net (code "37") (name "Net-(U1-RBG)") (class "Default")
      (node (ref "C_BG") (pin "1") (pinfunction "1_1") (pintype "passive"))
      (node (ref "RBG") (pin "2") (pinfunction "2_2") (pintype "passive"))
      (node (ref "U1") (pin "10") (pinfunction "RBG_10") (pintype "output"))
    )
    (net (code "38") (name "Net-(U1-RDCM)") (class "Default")
      (node (ref "RDCM") (pin "1") (pinfunction "1_1") (pintype "passive"))
      (node (ref "U1") (pin "8") (pinfunction "RDCM_8") (pintype "input"))
    )
    (net (code "39") (name "Net-(U1-RVOUT)") (class "Default")
      (node (ref "RVOUT") (pin "1") (pinfunction "1_1") (pintype "passive"))
      (node (ref "U1") (pin "9") (pinfunction "RVOUT_9") (pintype "output"))
    )
    (net (code "40") (name "Net-(U1-SOURCE)") (class "Default")
      (node (ref "C11") (pin "1") (pinfunction "1_1") (pintype "passive"))
      (node (ref "RPI1") (pin "2") (pinfunction "2_2") (pintype "passive"))
      (node (ref "U1") (pin "6") (pinfunction "SOURCE_6") (pintype "input"))
    )
    (net (code "41") (name "Net-(U2-GATE)") (class "Default")
      (node (ref "RGATE1") (pin "1") (pinfunction "1_1") (pintype "passive"))
      (node (ref "U2") (pin "7") (pinfunction "GATE_7") (pintype "bidirectional"))
    )
    (net (code "42") (name "Net-(U2-RBG)") (class "Default")
      (node (ref "C_BG1") (pin "1") (pinfunction "1_1") (pintype "passive"))
      (node (ref "RBG1") (pin "2") (pinfunction "2_2") (pintype "passive"))
      (node (ref "U2") (pin "10") (pinfunction "RBG_10") (pintype "output"))
    )
    (net (code "43") (name "Net-(U2-RDCM)") (class "Default")
      (node (ref "RDCM1") (pin "1") (pinfunction "1_1") (pintype "passive"))
      (node (ref "U2") (pin "8") (pinfunction "RDCM_8") (pintype "input"))
    )
    (net (code "44") (name "Net-(U2-RVOUT)") (class "Default")
      (node (ref "RVOUT1") (pin "1") (pinfunction "1_1") (pintype "passive"))
      (node (ref "U2") (pin "9") (pinfunction "RVOUT_9") (pintype "output"))
    )
    (net (code "45") (name "Net-(U2-SOURCE)") (class "Default")
      (node (ref "C6") (pin "1") (pinfunction "1_1") (pintype "passive"))
      (node (ref "RPI5") (pin "2") (pinfunction "2_2") (pintype "passive"))
      (node (ref "U2") (pin "6") (pinfunction "SOURCE_6") (pintype "input"))
    )
    (net (code "46") (name "Net-(U3-1A)") (class "Default")
      (node (ref "C15") (pin "2") (pinfunction "2_2") (pintype "passive"))
      (node (ref "FERRITE1") (pin "2") (pinfunction "2_2") (pintype "passive"))
      (node (ref "U3") (pin "P$1") (pinfunction "1A_P$1") (pintype "bidirectional"))
    )
    (net (code "47") (name "Net-(U3-1Y)") (class "Default")
      (node (ref "U3") (pin "P$3") (pinfunction "2A_P$3") (pintype "bidirectional"))
      (node (ref "U3") (pin "P$6") (pinfunction "1Y_P$6") (pintype "bidirectional"))
    )
    (net (code "48") (name "SGND") (class "Default")
      (node (ref "ADUM163N") (pin "8") (pinfunction "GND1_8") (pintype "passive"))
      (node (ref "ISO_IN") (pin "2") (pinfunction "2_2") (pintype "passive"))
      (node (ref "J1") (pin "1") (pinfunction "1_1") (pintype "passive"))
      (node (ref "PD_FI") (pin "1") (pinfunction "1_1") (pintype "passive"))
      (node (ref "PD_II") (pin "1") (pinfunction "1_1") (pintype "passive"))
      (node (ref "PD_MI") (pin "1") (pinfunction "1_1") (pintype "passive"))
    )
    (net (code "49") (name "SMT_OUT") (class "Default")
      (node (ref "ADUM163N") (pin "6") (pinfunction "VOE_6") (pintype "passive"))
      (node (ref "J1") (pin "3") (pinfunction "3_3") (pintype "passive"))
    )
    (net (code "50") (name "VBAT") (class "Default")
      (node (ref "C7") (pin "1") (pinfunction "1_1") (pintype "passive"))
      (node (ref "PWR") (pin "1") (pinfunction "1_1") (pintype "passive"))
      (node (ref "PWR") (pin "4") (pinfunction "4_4") (pintype "passive"))
      (node (ref "PWR") (pin "5") (pinfunction "5_5") (pintype "passive"))
      (node (ref "PWR") (pin "8") (pinfunction "8_8") (pintype "passive"))
      (node (ref "U$4") (pin "1") (pinfunction "P$1_1") (pintype "bidirectional"))
      (node (ref "U$7") (pin "1") (pinfunction "P$1_1") (pintype "bidirectional"))
      (node (ref "U$8") (pin "1") (pinfunction "P$1_1") (pintype "bidirectional"))
    )
    (net (code "51") (name "VLDO") (class "Default")
      (node (ref "ADUM163N") (pin "16") (pinfunction "VDD2_16") (pintype "passive"))
      (node (ref "C12") (pin "A") (pinfunction "+_A") (pintype "passive"))
      (node (ref "C159") (pin "2") (pinfunction "2_2") (pintype "passive"))
      (node (ref "C3") (pin "1") (pinfunction "1_1") (pintype "passive"))
      (node (ref "C5") (pin "2") (pinfunction "2_2") (pintype "passive"))
      (node (ref "C56") (pin "1") (pinfunction "1_1") (pintype "passive"))
      (node (ref "ISO_OUT") (pin "1") (pinfunction "1_1") (pintype "passive"))
      (node (ref "LDO") (pin "P$5") (pinfunction "OUT_P$5") (pintype "bidirectional"))
      (node (ref "R!DONE") (pin "2") (pinfunction "2_2") (pintype "passive"))
      (node (ref "R!DONE1") (pin "1") (pinfunction "1_1") (pintype "passive"))
      (node (ref "U3") (pin "P$5") (pinfunction "VCC_P$5") (pintype "bidirectional"))
    )
    (net (code "52") (name "VSIG") (class "Default")
      (node (ref "ADUM163N") (pin "1") (pinfunction "VDD1_1") (pintype "passive"))
      (node (ref "ISO_IN") (pin "1") (pinfunction "1_1") (pintype "passive"))
      (node (ref "J1") (pin "8") (pinfunction "8_8") (pintype "passive"))
    )
    (net (code "53") (name "VTRANS_PWR") (class "Default")
      (node (ref "C157") (pin "1") (pinfunction "1_1") (pintype "passive"))
      (node (ref "C158") (pin "1") (pinfunction "1_1") (pintype "passive"))
      (node (ref "C4") (pin "1") (pinfunction "1_1") (pintype "passive"))
      (node (ref "C8") (pin "1") (pinfunction "1_1") (pintype "passive"))
      (node (ref "C9") (pin "1") (pinfunction "1_1") (pintype "passive"))
      (node (ref "C_TRANS") (pin "1") (pinfunction "1_1") (pintype "passive"))
      (node (ref "C_TRANS1") (pin "1") (pinfunction "1_1") (pintype "passive"))
      (node (ref "C_VCC1") (pin "1") (pinfunction "1_1") (pintype "passive"))
      (node (ref "C_VCC2") (pin "1") (pinfunction "1_1") (pintype "passive"))
      (node (ref "LDO") (pin "P$1") (pinfunction "IN_P$1") (pintype "bidirectional"))
      (node (ref "LDO") (pin "P$3") (pinfunction "EN_P$3") (pintype "bidirectional"))
      (node (ref "LED!DONE") (pin "A") (pinfunction "A_A") (pintype "passive"))
      (node (ref "LED!DONE1") (pin "A") (pinfunction "A_A") (pintype "passive"))
      (node (ref "U$1") (pin "P$3") (pinfunction "P$3_P$3") (pintype "bidirectional"))
      (node (ref "U$1") (pin "P$4") (pinfunction "P$4_P$4") (pintype "bidirectional"))
      (node (ref "U$1") (pin "P$5") (pinfunction "P$5_P$5") (pintype "bidirectional"))
      (node (ref "U$1") (pin "P$6") (pinfunction "P$6_P$6") (pintype "bidirectional"))
      (node (ref "U$10") (pin "POS") (pinfunction "POS_POS") (pintype "bidirectional"))
      (node (ref "U$11") (pin "POS") (pinfunction "POS_POS") (pintype "bidirectional"))
      (node (ref "U$12") (pin "POS") (pinfunction "POS_POS") (pintype "bidirectional"))
      (node (ref "U$13") (pin "POS") (pinfunction "POS_POS") (pintype "bidirectional"))
      (node (ref "U$2") (pin "P$3") (pinfunction "P$3_P$3") (pintype "bidirectional"))
      (node (ref "U$2") (pin "P$4") (pinfunction "P$4_P$4") (pintype "bidirectional"))
      (node (ref "U$2") (pin "P$5") (pinfunction "P$5_P$5") (pintype "bidirectional"))
      (node (ref "U$2") (pin "P$6") (pinfunction "P$6_P$6") (pintype "bidirectional"))
      (node (ref "U$4") (pin "2") (pinfunction "P$2_2") (pintype "bidirectional"))
      (node (ref "U$7") (pin "2") (pinfunction "P$2_2") (pintype "bidirectional"))
      (node (ref "U$8") (pin "2") (pinfunction "P$2_2") (pintype "bidirectional"))
      (node (ref "U1") (pin "1") (pinfunction "VTRANS_1") (pintype "power_in"))
      (node (ref "U1") (pin "4") (pinfunction "VCC_4") (pintype "power_in"))
      (node (ref "U2") (pin "1") (pinfunction "VTRANS_1") (pintype "power_in"))
      (node (ref "U2") (pin "4") (pinfunction "VCC_4") (pintype "power_in"))
      (node (ref "U4") (pin "P$1") (pinfunction "VS_P$1") (pintype "bidirectional"))
      (node (ref "U4") (pin "P$8") (pinfunction "VS2_P$8") (pintype "bidirectional"))
    )
    (net (code "54") (name "unconnected-(U$1-PadP$2)") (class "Default")
      (node (ref "U$1") (pin "P$2") (pinfunction "P$2_P$2") (pintype "bidirectional"))
    )
    (net (code "55") (name "unconnected-(U$1-PadP$11)") (class "Default")
      (node (ref "U$1") (pin "P$11") (pinfunction "P$11_P$11") (pintype "bidirectional"))
    )
    (net (code "56") (name "unconnected-(U$2-PadP$2)") (class "Default")
      (node (ref "U$2") (pin "P$2") (pinfunction "P$2_P$2") (pintype "bidirectional"))
    )
    (net (code "57") (name "unconnected-(U$2-PadP$11)") (class "Default")
      (node (ref "U$2") (pin "P$11") (pinfunction "P$11_P$11") (pintype "bidirectional"))
    )
    (net (code "58") (name "unconnected-(U4-NC-PadP$3)") (class "Default")
      (node (ref "U4") (pin "P$3") (pinfunction "NC_P$3") (pintype "bidirectional"))
    )
  )
)
